# Grove_-_Temperature_Humidity_Pressure_an.net
KiCad netlist of a schematic drawn in EAGLE
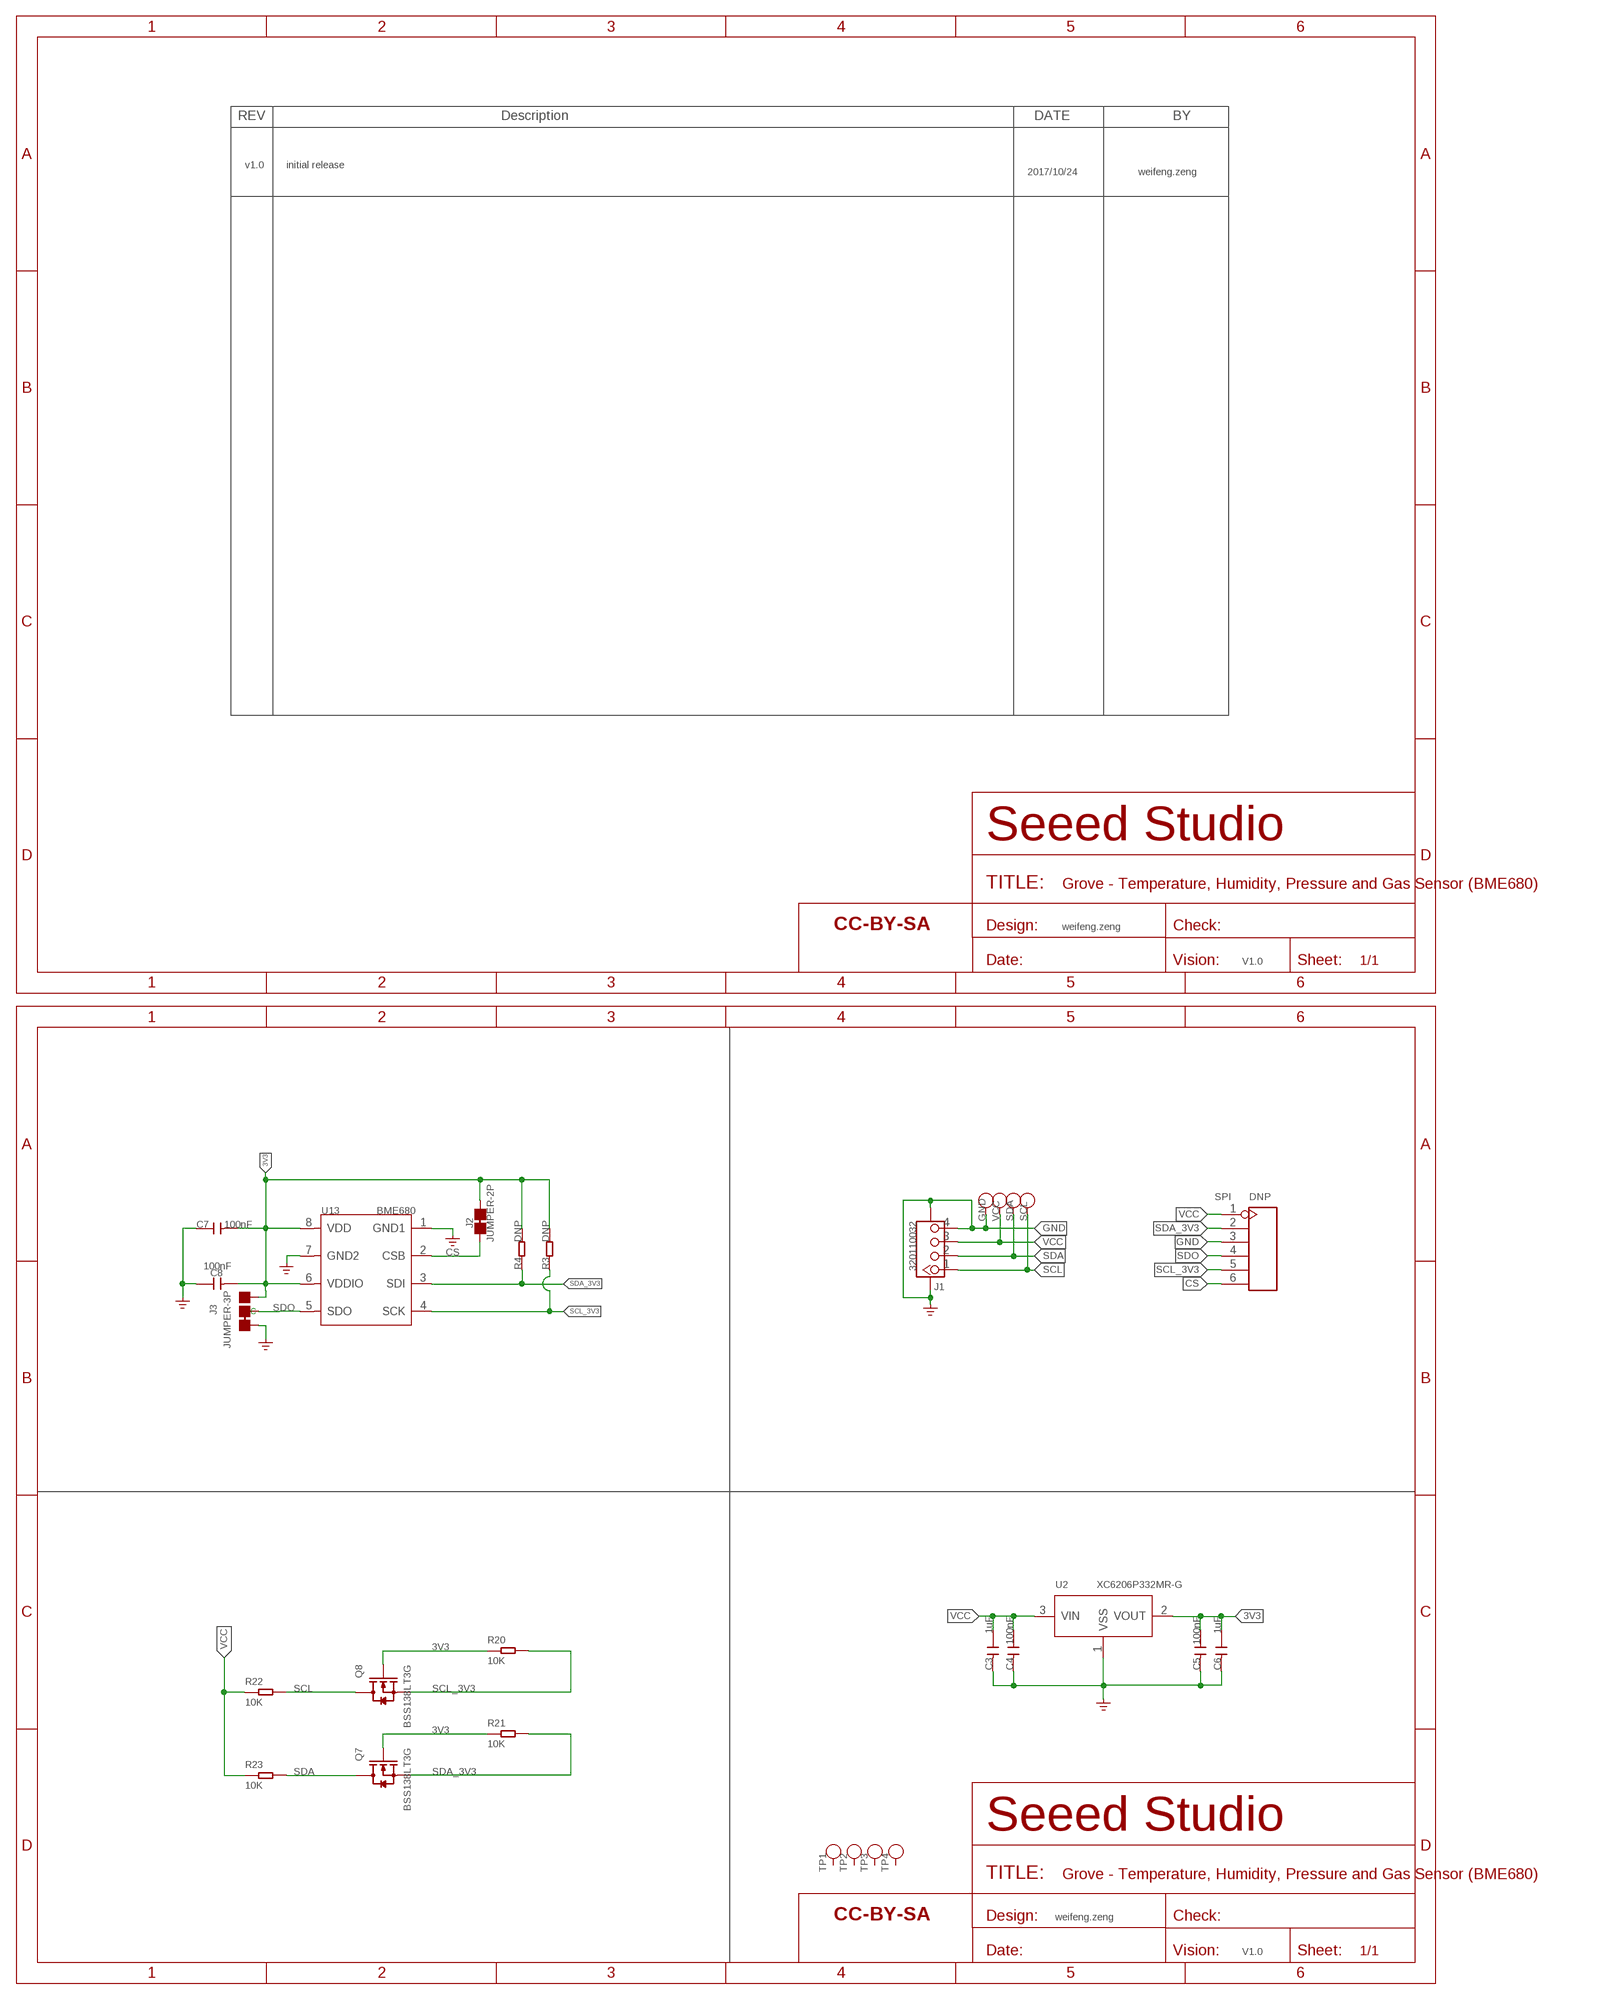
[diagram p0: schematic, sheet 1]

(export (version "E")
  (design (tool "Eeschema 10.0.6"))
  (components
    (comp (ref "C3")
      (value "1uF")
      (footprint "eagle-import:C0603")
      (libsource (lib "eagle-import") (part "CAP-0603"))
    )
    (comp (ref "C4")
      (value "100nF")
      (footprint "eagle-import:C0603")
      (libsource (lib "eagle-import") (part "CAP-0603"))
    )
    (comp (ref "C5")
      (value "100nF")
      (footprint "eagle-import:C0603")
      (libsource (lib "eagle-import") (part "CAP-0603"))
    )
    (comp (ref "C6")
      (value "1uF")
      (footprint "eagle-import:C0603")
      (libsource (lib "eagle-import") (part "CAP-0603"))
    )
    (comp (ref "C7")
      (value "100nF")
      (footprint "eagle-import:C0603")
      (libsource (lib "eagle-import") (part "CAP-0603"))
    )
    (comp (ref "C8")
      (value "100nF")
      (footprint "eagle-import:C0603")
      (libsource (lib "eagle-import") (part "CAP-0603"))
    )
    (comp (ref "FR1")
      (value "SEEEDSTUDIO-OPEN-SCH-FRAME")
      (footprint "eagle-import:SEEEDSTUDIO-PCB-FRAME")
      (libsource (lib "eagle-import") (part "SEEEDSTUDIO-OPEN-SCH-FRAME"))
    )
    (comp (ref "FR2")
      (value "SEEEDSTUDIO-OPEN-SCH-FRAME")
      (footprint "eagle-import:SEEEDSTUDIO-PCB-FRAME")
      (libsource (lib "eagle-import") (part "SEEEDSTUDIO-OPEN-SCH-FRAME"))
    )
    (comp (ref "GND")
      (value "TEST-POINT'4545'")
      (footprint "eagle-import:TP-D45MIL")
      (fields (field (name "PARTNO") "DNP"))
      (libsource (lib "eagle-import") (part "TEST-POINT'4545'"))
    )
    (comp (ref "J1")
      (value "320110032")
      (footprint "eagle-import:HW4-SMD-2.0-90D")
      (libsource (lib "eagle-import") (part "GROVE-CONNECTOR-SMD'90D'"))
    )
    (comp (ref "J2")
      (value "JUMPER-2P")
      (footprint "eagle-import:2P-SMD-SHORT")
      (libsource (lib "eagle-import") (part "JUMPER-2P-SHORT"))
    )
    (comp (ref "J3")
      (value "JUMPER-3P")
      (footprint "eagle-import:3P-SMD-SHORT")
      (libsource (lib "eagle-import") (part "JUMPER-3P-SHORT"))
    )
    (comp (ref "Q7")
      (value "BSS138LT3G")
      (footprint "eagle-import:SOT-23")
      (libsource (lib "eagle-import") (part "MOSFET-N'SOT23'"))
    )
    (comp (ref "Q8")
      (value "BSS138LT3G")
      (footprint "eagle-import:SOT-23")
      (libsource (lib "eagle-import") (part "MOSFET-N'SOT23'"))
    )
    (comp (ref "R3")
      (value "DNP")
      (footprint "eagle-import:R0603")
      (libsource (lib "eagle-import") (part "RES-0603"))
    )
    (comp (ref "R4")
      (value "DNP")
      (footprint "eagle-import:R0603")
      (libsource (lib "eagle-import") (part "RES-0603"))
    )
    (comp (ref "R20")
      (value "10K")
      (footprint "eagle-import:R0603")
      (libsource (lib "eagle-import") (part "RES-0603"))
    )
    (comp (ref "R21")
      (value "10K")
      (footprint "eagle-import:R0603")
      (libsource (lib "eagle-import") (part "RES-0603"))
    )
    (comp (ref "R22")
      (value "10K")
      (footprint "eagle-import:R0603")
      (libsource (lib "eagle-import") (part "RES-0603"))
    )
    (comp (ref "R23")
      (value "10K")
      (footprint "eagle-import:R0603")
      (libsource (lib "eagle-import") (part "RES-0603"))
    )
    (comp (ref "SCL")
      (value "TEST-POINT'4545'")
      (footprint "eagle-import:TP-D45MIL")
      (fields (field (name "PARTNO") "DNP"))
      (libsource (lib "eagle-import") (part "TEST-POINT'4545'"))
    )
    (comp (ref "SDA")
      (value "TEST-POINT'4545'")
      (footprint "eagle-import:TP-D45MIL")
      (fields (field (name "PARTNO") "DNP"))
      (libsource (lib "eagle-import") (part "TEST-POINT'4545'"))
    )
    (comp (ref "SPI")
      (value "DNP")
      (footprint "eagle-import:H6-2.54-C65D35MIL")
      (libsource (lib "eagle-import") (part "HEADER-6P-65/35MIL"))
    )
    (comp (ref "TP1")
      (value "TEST-POINT'4545'")
      (footprint "eagle-import:TP-D45MIL")
      (fields (field (name "PARTNO") "DNP"))
      (libsource (lib "eagle-import") (part "TEST-POINT'4545'"))
    )
    (comp (ref "TP2")
      (value "TEST-POINT'4545'")
      (footprint "eagle-import:TP-D45MIL")
      (fields (field (name "PARTNO") "DNP"))
      (libsource (lib "eagle-import") (part "TEST-POINT'4545'"))
    )
    (comp (ref "TP3")
      (value "TEST-POINT'4545'")
      (footprint "eagle-import:TP-D45MIL")
      (fields (field (name "PARTNO") "DNP"))
      (libsource (lib "eagle-import") (part "TEST-POINT'4545'"))
    )
    (comp (ref "TP4")
      (value "TEST-POINT'4545'")
      (footprint "eagle-import:TP-D45MIL")
      (fields (field (name "PARTNO") "DNP"))
      (libsource (lib "eagle-import") (part "TEST-POINT'4545'"))
    )
    (comp (ref "U2")
      (value "XC6206P332MR-G")
      (footprint "eagle-import:SOT-23")
      (libsource (lib "eagle-import") (part "PMIC-XC6206PMR"))
    )
    (comp (ref "U13")
      (value "BME680")
      (footprint "eagle-import:SNR8-0.8-3X3X0.93MM")
      (libsource (lib "eagle-import") (part "SENSOR-BME680"))
    )
    (comp (ref "VCC")
      (value "TEST-POINT'4545'")
      (footprint "eagle-import:TP-D45MIL")
      (fields (field (name "PARTNO") "DNP"))
      (libsource (lib "eagle-import") (part "TEST-POINT'4545'"))
    )
  )
  (nets
    (net (code "1") (name "3V3") (class "Default")
      (node (ref "C5") (pin "1") (pinfunction "1_1") (pintype "passive"))
      (node (ref "C6") (pin "1") (pinfunction "1_1") (pintype "passive"))
      (node (ref "C7") (pin "2") (pinfunction "2_2") (pintype "passive"))
      (node (ref "C8") (pin "2") (pinfunction "2_2") (pintype "passive"))
      (node (ref "J2") (pin "2") (pinfunction "2_2") (pintype "bidirectional"))
      (node (ref "J3") (pin "00") (pinfunction "R_00") (pintype "bidirectional"))
      (node (ref "Q7") (pin "1") (pinfunction "G_1") (pintype "passive"))
      (node (ref "Q8") (pin "1") (pinfunction "G_1") (pintype "passive"))
      (node (ref "R20") (pin "1") (pinfunction "1_1") (pintype "passive"))
      (node (ref "R21") (pin "1") (pinfunction "1_1") (pintype "passive"))
      (node (ref "R3") (pin "2") (pinfunction "2_2") (pintype "passive"))
      (node (ref "R4") (pin "2") (pinfunction "2_2") (pintype "passive"))
      (node (ref "U13") (pin "6") (pinfunction "VDDIO_6") (pintype "bidirectional"))
      (node (ref "U13") (pin "8") (pinfunction "VDD_8") (pintype "bidirectional"))
      (node (ref "U2") (pin "2") (pinfunction "VOUT_2") (pintype "bidirectional"))
    )
    (net (code "2") (name "CS") (class "Default")
      (node (ref "J2") (pin "1") (pinfunction "1_1") (pintype "bidirectional"))
      (node (ref "SPI") (pin "6") (pinfunction "6_6") (pintype "bidirectional"))
      (node (ref "U13") (pin "2") (pinfunction "CSB_2") (pintype "bidirectional"))
    )
    (net (code "3") (name "GND") (class "Default")
      (node (ref "C3") (pin "2") (pinfunction "2_2") (pintype "passive"))
      (node (ref "C4") (pin "2") (pinfunction "2_2") (pintype "passive"))
      (node (ref "C5") (pin "2") (pinfunction "2_2") (pintype "passive"))
      (node (ref "C6") (pin "2") (pinfunction "2_2") (pintype "passive"))
      (node (ref "C7") (pin "1") (pinfunction "1_1") (pintype "passive"))
      (node (ref "C8") (pin "1") (pinfunction "1_1") (pintype "passive"))
      (node (ref "GND") (pin "T") (pinfunction "T_T") (pintype "bidirectional"))
      (node (ref "J1") (pin "4") (pinfunction "4_4") (pintype "bidirectional"))
      (node (ref "J1") (pin "SS1") (pinfunction "SS1_SS1") (pintype "bidirectional"))
      (node (ref "J1") (pin "SS2") (pinfunction "SS2_SS2") (pintype "bidirectional"))
      (node (ref "J3") (pin "11") (pinfunction "L_11") (pintype "bidirectional"))
      (node (ref "SPI") (pin "3") (pinfunction "3_3") (pintype "bidirectional"))
      (node (ref "U13") (pin "1") (pinfunction "GND1_1") (pintype "bidirectional"))
      (node (ref "U13") (pin "7") (pinfunction "GND2_7") (pintype "bidirectional"))
      (node (ref "U2") (pin "1") (pinfunction "VSS_1") (pintype "bidirectional"))
    )
    (net (code "4") (name "SCL") (class "Default")
      (node (ref "J1") (pin "1") (pinfunction "1_1") (pintype "bidirectional"))
      (node (ref "Q8") (pin "3") (pinfunction "D_3") (pintype "passive"))
      (node (ref "R22") (pin "2") (pinfunction "2_2") (pintype "passive"))
      (node (ref "SCL") (pin "T") (pinfunction "T_T") (pintype "bidirectional"))
    )
    (net (code "5") (name "SCL_3V3") (class "Default")
      (node (ref "Q8") (pin "2") (pinfunction "S_2") (pintype "passive"))
      (node (ref "R20") (pin "2") (pinfunction "2_2") (pintype "passive"))
      (node (ref "R3") (pin "1") (pinfunction "1_1") (pintype "passive"))
      (node (ref "SPI") (pin "5") (pinfunction "5_5") (pintype "bidirectional"))
      (node (ref "U13") (pin "4") (pinfunction "SCK_4") (pintype "bidirectional"))
    )
    (net (code "6") (name "SDA") (class "Default")
      (node (ref "J1") (pin "2") (pinfunction "2_2") (pintype "bidirectional"))
      (node (ref "Q7") (pin "3") (pinfunction "D_3") (pintype "passive"))
      (node (ref "R23") (pin "2") (pinfunction "2_2") (pintype "passive"))
      (node (ref "SDA") (pin "T") (pinfunction "T_T") (pintype "bidirectional"))
    )
    (net (code "7") (name "SDA_3V3") (class "Default")
      (node (ref "Q7") (pin "2") (pinfunction "S_2") (pintype "passive"))
      (node (ref "R21") (pin "2") (pinfunction "2_2") (pintype "passive"))
      (node (ref "R4") (pin "1") (pinfunction "1_1") (pintype "passive"))
      (node (ref "SPI") (pin "2") (pinfunction "2_2") (pintype "bidirectional"))
      (node (ref "U13") (pin "3") (pinfunction "SDI_3") (pintype "bidirectional"))
    )
    (net (code "8") (name "SDO") (class "Default")
      (node (ref "J3") (pin "MM") (pinfunction "C_MM") (pintype "bidirectional"))
      (node (ref "SPI") (pin "4") (pinfunction "4_4") (pintype "bidirectional"))
      (node (ref "U13") (pin "5") (pinfunction "SDO_5") (pintype "bidirectional"))
    )
    (net (code "9") (name "VCC") (class "Default")
      (node (ref "C3") (pin "1") (pinfunction "1_1") (pintype "passive"))
      (node (ref "C4") (pin "1") (pinfunction "1_1") (pintype "passive"))
      (node (ref "J1") (pin "3") (pinfunction "3_3") (pintype "bidirectional"))
      (node (ref "R22") (pin "1") (pinfunction "1_1") (pintype "passive"))
      (node (ref "R23") (pin "1") (pinfunction "1_1") (pintype "passive"))
      (node (ref "SPI") (pin "1") (pinfunction "1_1") (pintype "bidirectional"))
      (node (ref "U2") (pin "3") (pinfunction "VIN_3") (pintype "bidirectional"))
      (node (ref "VCC") (pin "T") (pinfunction "T_T") (pintype "bidirectional"))
    )
    (net (code "10") (name "unconnected-(TP1-PadT)") (class "Default")
      (node (ref "TP1") (pin "T") (pinfunction "T_T") (pintype "bidirectional"))
    )
    (net (code "11") (name "unconnected-(TP2-PadT)") (class "Default")
      (node (ref "TP2") (pin "T") (pinfunction "T_T") (pintype "bidirectional"))
    )
    (net (code "12") (name "unconnected-(TP3-PadT)") (class "Default")
      (node (ref "TP3") (pin "T") (pinfunction "T_T") (pintype "bidirectional"))
    )
    (net (code "13") (name "unconnected-(TP4-PadT)") (class "Default")
      (node (ref "TP4") (pin "T") (pinfunction "T_T") (pintype "bidirectional"))
    )
  )
)
